# Spring2020V1_2.net
KiCad netlist of a schematic drawn in EAGLE
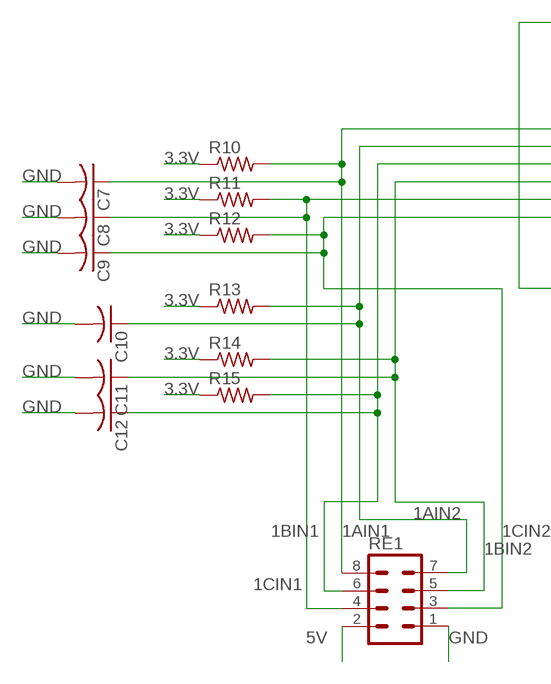
[diagram p0: schematic, sheet 1, part 1 of 2]
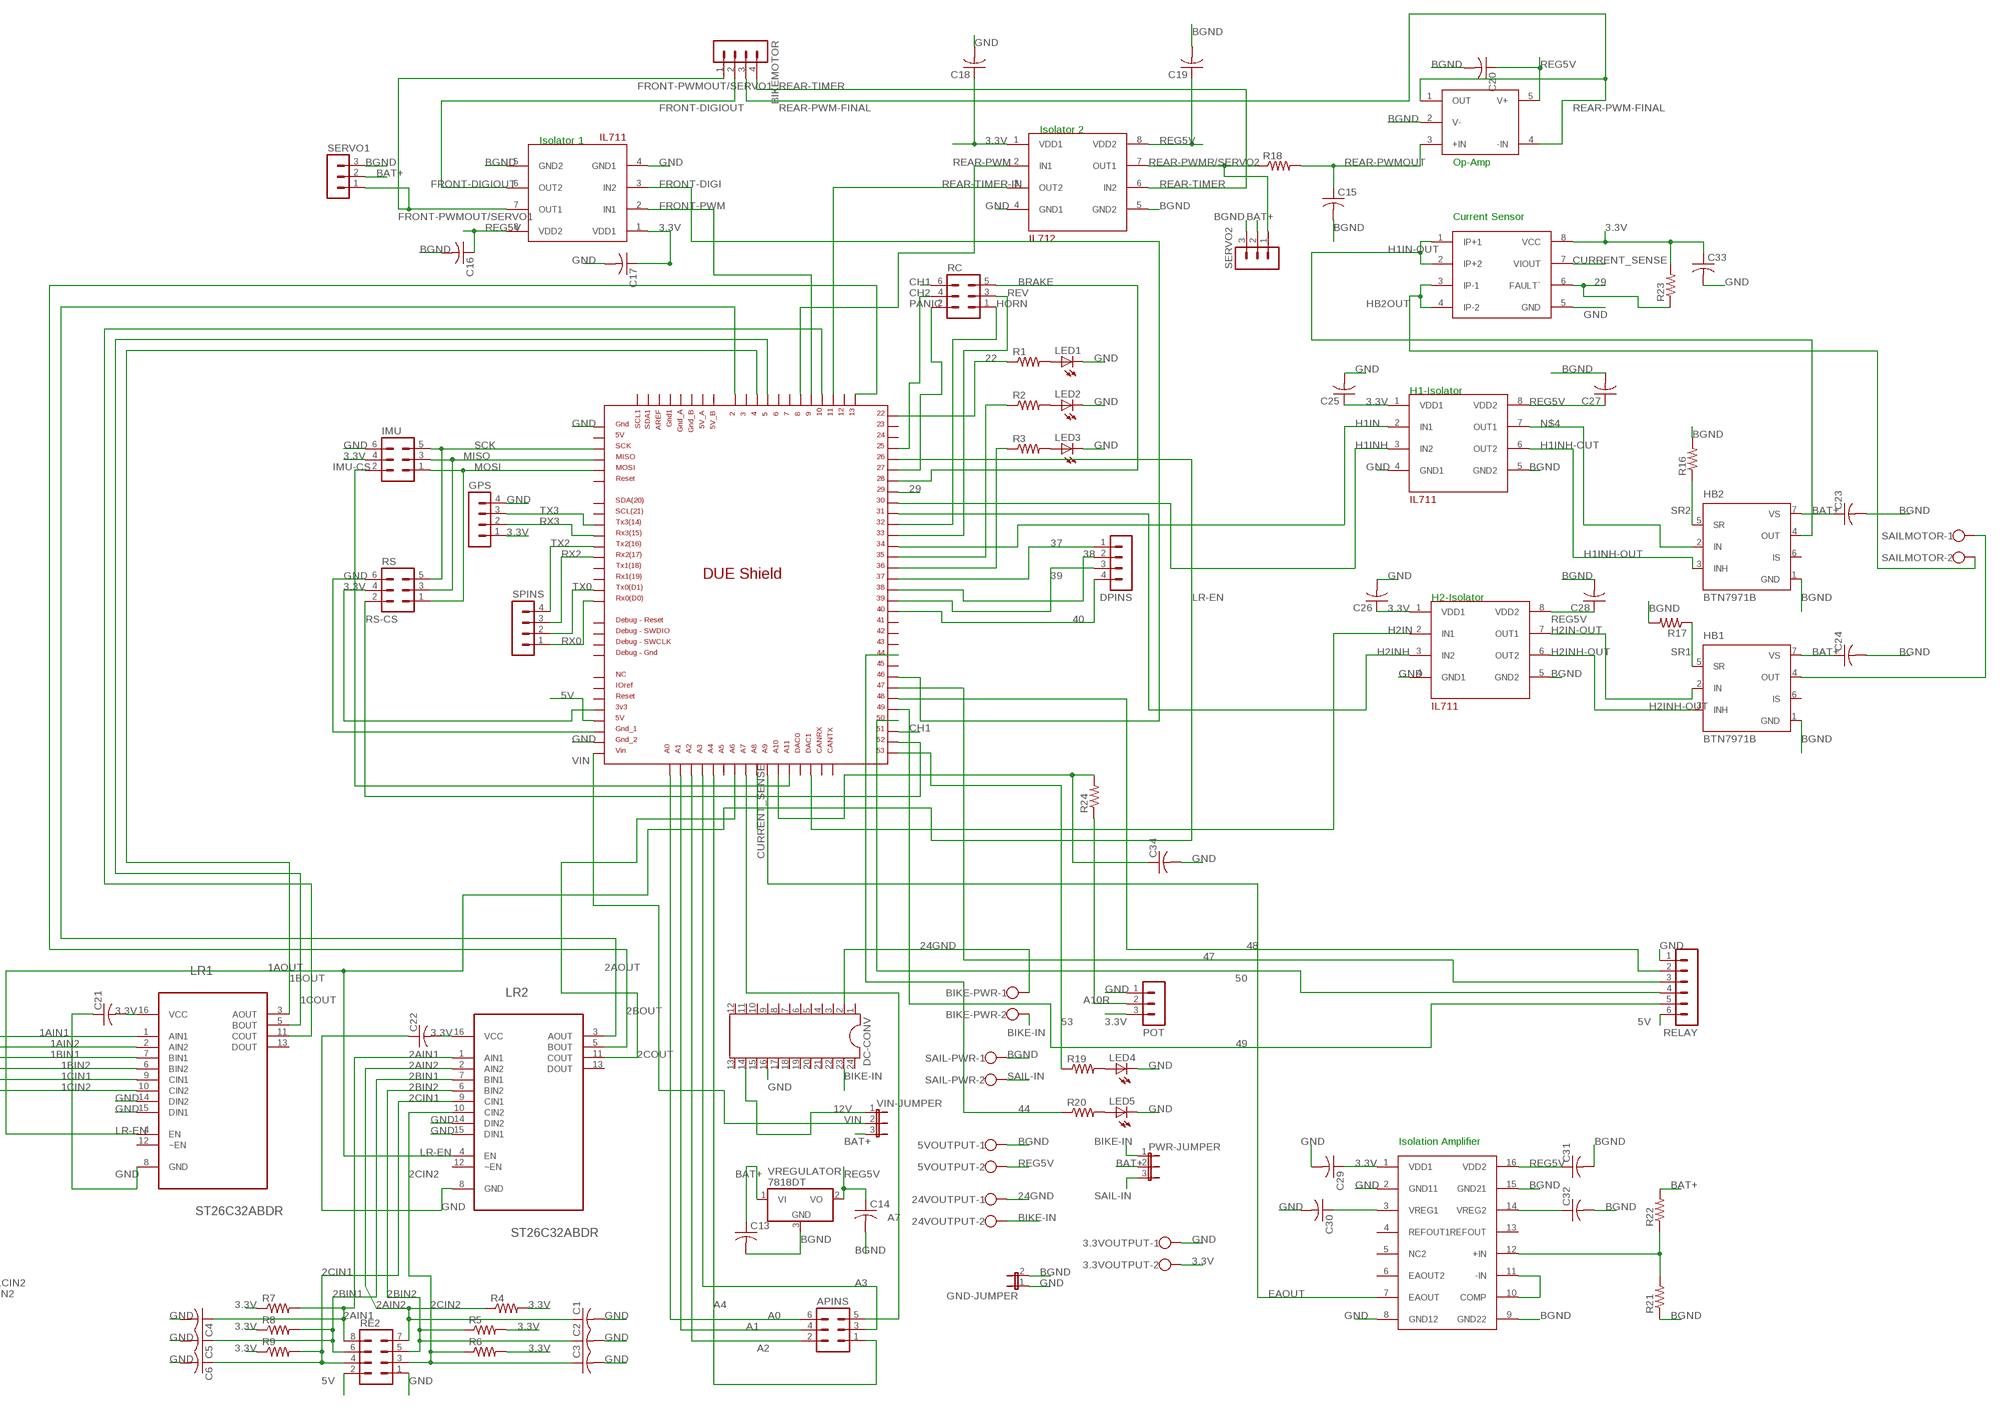
[diagram p1: schematic, sheet 1, part 2 of 2]

(export (version "E")
  (design (tool "Eeschema 10.0.6"))
  (components
    (comp (ref "3.3VOUTPUT")
      (value "W237-102")
      (footprint "eagle-import:W237-102")
      (fields (field (name "MPN") "237-102"))
      (libsource (lib "eagle-import") (part "W237-102"))
    )
    (comp (ref "5VOUTPUT")
      (value "W237-102")
      (footprint "eagle-import:W237-102")
      (fields (field (name "MPN") "237-102"))
      (libsource (lib "eagle-import") (part "W237-102"))
    )
    (comp (ref "24VOUTPUT")
      (value "W237-102")
      (footprint "eagle-import:W237-102")
      (fields (field (name "MPN") "237-102"))
      (libsource (lib "eagle-import") (part "W237-102"))
    )
    (comp (ref "APINS")
      (value "MA03-2")
      (footprint "eagle-import:MA03-2")
      (libsource (lib "eagle-import") (part "MA03-2"))
    )
    (comp (ref "BIKE-PWR")
      (value "W237-102")
      (footprint "eagle-import:W237-102")
      (fields (field (name "MPN") "237-102"))
      (libsource (lib "eagle-import") (part "W237-102"))
    )
    (comp (ref "BIKEMOTOR")
      (value "MA04-1")
      (footprint "eagle-import:MA04-1")
      (libsource (lib "eagle-import") (part "MA04-1"))
    )
    (comp (ref "C1")
      (value "C-US025-025X050")
      (footprint "eagle-import:C025-025X050")
      (libsource (lib "eagle-import") (part "C-US025-025X050"))
    )
    (comp (ref "C2")
      (value "C-US025-025X050")
      (footprint "eagle-import:C025-025X050")
      (libsource (lib "eagle-import") (part "C-US025-025X050"))
    )
    (comp (ref "C3")
      (value "C-US025-025X050")
      (footprint "eagle-import:C025-025X050")
      (libsource (lib "eagle-import") (part "C-US025-025X050"))
    )
    (comp (ref "C4")
      (value "C-US025-025X050")
      (footprint "eagle-import:C025-025X050")
      (libsource (lib "eagle-import") (part "C-US025-025X050"))
    )
    (comp (ref "C5")
      (value "C-US025-025X050")
      (footprint "eagle-import:C025-025X050")
      (libsource (lib "eagle-import") (part "C-US025-025X050"))
    )
    (comp (ref "C6")
      (value "C-US025-025X050")
      (footprint "eagle-import:C025-025X050")
      (libsource (lib "eagle-import") (part "C-US025-025X050"))
    )
    (comp (ref "C7")
      (value "C-US025-025X050")
      (footprint "eagle-import:C025-025X050")
      (libsource (lib "eagle-import") (part "C-US025-025X050"))
    )
    (comp (ref "C8")
      (value "C-US025-025X050")
      (footprint "eagle-import:C025-025X050")
      (libsource (lib "eagle-import") (part "C-US025-025X050"))
    )
    (comp (ref "C9")
      (value "C-US025-025X050")
      (footprint "eagle-import:C025-025X050")
      (libsource (lib "eagle-import") (part "C-US025-025X050"))
    )
    (comp (ref "C10")
      (value "C-US025-025X050")
      (footprint "eagle-import:C025-025X050")
      (libsource (lib "eagle-import") (part "C-US025-025X050"))
    )
    (comp (ref "C11")
      (value "C-US025-025X050")
      (footprint "eagle-import:C025-025X050")
      (libsource (lib "eagle-import") (part "C-US025-025X050"))
    )
    (comp (ref "C12")
      (value "C-US025-025X050")
      (footprint "eagle-import:C025-025X050")
      (libsource (lib "eagle-import") (part "C-US025-025X050"))
    )
    (comp (ref "C13")
      (value "C-US025-050X050")
      (footprint "eagle-import:C025-050X050")
      (libsource (lib "eagle-import") (part "C-US025-050X050"))
    )
    (comp (ref "C14")
      (value "C-US025-050X050")
      (footprint "eagle-import:C025-050X050")
      (libsource (lib "eagle-import") (part "C-US025-050X050"))
    )
    (comp (ref "C15")
      (value "C-US025-050X050")
      (footprint "eagle-import:C025-050X050")
      (libsource (lib "eagle-import") (part "C-US025-050X050"))
    )
    (comp (ref "C16")
      (value "C-US025-050X050")
      (footprint "eagle-import:C025-050X050")
      (libsource (lib "eagle-import") (part "C-US025-050X050"))
    )
    (comp (ref "C17")
      (value "C-US025-050X050")
      (footprint "eagle-import:C025-050X050")
      (libsource (lib "eagle-import") (part "C-US025-050X050"))
    )
    (comp (ref "C18")
      (value "C-US025-050X050")
      (footprint "eagle-import:C025-050X050")
      (libsource (lib "eagle-import") (part "C-US025-050X050"))
    )
    (comp (ref "C19")
      (value "C-US025-050X050")
      (footprint "eagle-import:C025-050X050")
      (libsource (lib "eagle-import") (part "C-US025-050X050"))
    )
    (comp (ref "C20")
      (value "C-US025-050X050")
      (footprint "eagle-import:C025-050X050")
      (libsource (lib "eagle-import") (part "C-US025-050X050"))
    )
    (comp (ref "C21")
      (value "C-US025-050X050")
      (footprint "eagle-import:C025-050X050")
      (libsource (lib "eagle-import") (part "C-US025-050X050"))
    )
    (comp (ref "C22")
      (value "C-US025-050X050")
      (footprint "eagle-import:C025-050X050")
      (libsource (lib "eagle-import") (part "C-US025-050X050"))
    )
    (comp (ref "C23")
      (value "C-US150-091X182")
      (footprint "eagle-import:C150-091X182")
      (libsource (lib "eagle-import") (part "C-US150-091X182"))
    )
    (comp (ref "C24")
      (value "C-US150-091X182")
      (footprint "eagle-import:C150-091X182")
      (libsource (lib "eagle-import") (part "C-US150-091X182"))
    )
    (comp (ref "C25")
      (value "C-US025-050X050")
      (footprint "eagle-import:C025-050X050")
      (libsource (lib "eagle-import") (part "C-US025-050X050"))
    )
    (comp (ref "C26")
      (value "C-US025-050X050")
      (footprint "eagle-import:C025-050X050")
      (libsource (lib "eagle-import") (part "C-US025-050X050"))
    )
    (comp (ref "C27")
      (value "C-US025-050X050")
      (footprint "eagle-import:C025-050X050")
      (libsource (lib "eagle-import") (part "C-US025-050X050"))
    )
    (comp (ref "C28")
      (value "C-US025-050X050")
      (footprint "eagle-import:C025-050X050")
      (libsource (lib "eagle-import") (part "C-US025-050X050"))
    )
    (comp (ref "C29")
      (value "C-US025-050X050")
      (footprint "eagle-import:C025-050X050")
      (libsource (lib "eagle-import") (part "C-US025-050X050"))
    )
    (comp (ref "C30")
      (value "C-US025-050X050")
      (footprint "eagle-import:C025-050X050")
      (libsource (lib "eagle-import") (part "C-US025-050X050"))
    )
    (comp (ref "C31")
      (value "C-US025-050X050")
      (footprint "eagle-import:C025-050X050")
      (libsource (lib "eagle-import") (part "C-US025-050X050"))
    )
    (comp (ref "C32")
      (value "C-US025-050X050")
      (footprint "eagle-import:C025-050X050")
      (libsource (lib "eagle-import") (part "C-US025-050X050"))
    )
    (comp (ref "C33")
      (value "C-US025-050X050")
      (footprint "eagle-import:C025-050X050")
      (libsource (lib "eagle-import") (part "C-US025-050X050"))
    )
    (comp (ref "C34")
      (value "C-US025-050X050")
      (footprint "eagle-import:C025-050X050")
      (libsource (lib "eagle-import") (part "C-US025-050X050"))
    )
    (comp (ref "DC-CONV")
      (value "CU.INC---VAWQ6-Q48-S12H-6")
      (footprint "eagle-import:DIL24-6")
      (libsource (lib "eagle-import") (part "CU.INC---VAWQ6-Q48-S12H-6"))
    )
    (comp (ref "DPINS")
      (value "MA04-1")
      (footprint "eagle-import:MA04-1")
      (libsource (lib "eagle-import") (part "MA04-1"))
    )
    (comp (ref "GND-JUMPER")
      (value "JP1E")
      (footprint "eagle-import:JP1")
      (libsource (lib "eagle-import") (part "JP1E"))
    )
    (comp (ref "GPS")
      (value "MA04-1")
      (footprint "eagle-import:MA04-1")
      (libsource (lib "eagle-import") (part "MA04-1"))
    )
    (comp (ref "HB1")
      (value "BTN7971B")
      (footprint "eagle-import:P-TO263-7-1")
      (libsource (lib "eagle-import") (part "BTN7971B"))
    )
    (comp (ref "HB2")
      (value "BTN7971B")
      (footprint "eagle-import:P-TO263-7-1")
      (libsource (lib "eagle-import") (part "BTN7971B"))
    )
    (comp (ref "IMU")
      (value "MA03-2")
      (footprint "eagle-import:MA03-2")
      (libsource (lib "eagle-import") (part "MA03-2"))
    )
    (comp (ref "LED1")
      (value "LED5MM")
      (footprint "eagle-import:LED5MM")
      (libsource (lib "eagle-import") (part "LED5MM"))
    )
    (comp (ref "LED2")
      (value "LED5MM")
      (footprint "eagle-import:LED5MM")
      (libsource (lib "eagle-import") (part "LED5MM"))
    )
    (comp (ref "LED3")
      (value "LED5MM")
      (footprint "eagle-import:LED5MM")
      (libsource (lib "eagle-import") (part "LED5MM"))
    )
    (comp (ref "LED4")
      (value "LED5MM")
      (footprint "eagle-import:LED5MM")
      (libsource (lib "eagle-import") (part "LED5MM"))
    )
    (comp (ref "LED5")
      (value "LED5MM")
      (footprint "eagle-import:LED5MM")
      (libsource (lib "eagle-import") (part "LED5MM"))
    )
    (comp (ref "LR1")
      (value "ST26C32ABDR")
      (footprint "eagle-import:SOIC127P600X175-16N")
      (libsource (lib "eagle-import") (part "ST26C32ABDR"))
    )
    (comp (ref "LR2")
      (value "ST26C32ABDR")
      (footprint "eagle-import:SOIC127P600X175-16N")
      (libsource (lib "eagle-import") (part "ST26C32ABDR"))
    )
    (comp (ref "OP-AMP")
      (value "OPAMP")
      (footprint "eagle-import:SOT95P280X145-5N")
      (libsource (lib "eagle-import") (part "OPAMP"))
    )
    (comp (ref "POT")
      (value "MA03-1")
      (footprint "eagle-import:MA03-1")
      (libsource (lib "eagle-import") (part "MA03-1"))
    )
    (comp (ref "PWR-JUMPER")
      (value "JP2E")
      (footprint "eagle-import:JP2")
      (libsource (lib "eagle-import") (part "JP2E"))
    )
    (comp (ref "R1")
      (value "R-US_0309/10")
      (footprint "eagle-import:0309_10")
      (libsource (lib "eagle-import") (part "R-US_0309/10"))
    )
    (comp (ref "R2")
      (value "R-US_0309/10")
      (footprint "eagle-import:0309_10")
      (libsource (lib "eagle-import") (part "R-US_0309/10"))
    )
    (comp (ref "R3")
      (value "R-US_0309/10")
      (footprint "eagle-import:0309_10")
      (libsource (lib "eagle-import") (part "R-US_0309/10"))
    )
    (comp (ref "R4")
      (value "R-US_0613/15")
      (footprint "eagle-import:P0613_15")
      (libsource (lib "eagle-import") (part "resistor_R-US_0613/15"))
    )
    (comp (ref "R5")
      (value "R-US_0613/15")
      (footprint "eagle-import:P0613_15")
      (libsource (lib "eagle-import") (part "resistor_R-US_0613/15"))
    )
    (comp (ref "R6")
      (value "R-US_0613/15")
      (footprint "eagle-import:P0613_15")
      (libsource (lib "eagle-import") (part "resistor_R-US_0613/15"))
    )
    (comp (ref "R7")
      (value "R-US_0613/15")
      (footprint "eagle-import:P0613_15")
      (libsource (lib "eagle-import") (part "resistor_R-US_0613/15"))
    )
    (comp (ref "R8")
      (value "R-US_0613/15")
      (footprint "eagle-import:P0613_15")
      (libsource (lib "eagle-import") (part "resistor_R-US_0613/15"))
    )
    (comp (ref "R9")
      (value "R-US_0613/15")
      (footprint "eagle-import:P0613_15")
      (libsource (lib "eagle-import") (part "resistor_R-US_0613/15"))
    )
    (comp (ref "R10")
      (value "R-US_0613/15")
      (footprint "eagle-import:P0613_15")
      (libsource (lib "eagle-import") (part "resistor_R-US_0613/15"))
    )
    (comp (ref "R11")
      (value "R-US_0613/15")
      (footprint "eagle-import:P0613_15")
      (libsource (lib "eagle-import") (part "resistor_R-US_0613/15"))
    )
    (comp (ref "R12")
      (value "R-US_0613/15")
      (footprint "eagle-import:P0613_15")
      (libsource (lib "eagle-import") (part "resistor_R-US_0613/15"))
    )
    (comp (ref "R13")
      (value "R-US_0613/15")
      (footprint "eagle-import:P0613_15")
      (libsource (lib "eagle-import") (part "resistor_R-US_0613/15"))
    )
    (comp (ref "R14")
      (value "R-US_0613/15")
      (footprint "eagle-import:P0613_15")
      (libsource (lib "eagle-import") (part "resistor_R-US_0613/15"))
    )
    (comp (ref "R15")
      (value "R-US_0613/15")
      (footprint "eagle-import:P0613_15")
      (libsource (lib "eagle-import") (part "resistor_R-US_0613/15"))
    )
    (comp (ref "R16")
      (value "R-US_0613/15")
      (footprint "eagle-import:P0613_15")
      (libsource (lib "eagle-import") (part "resistor_R-US_0613/15"))
    )
    (comp (ref "R17")
      (value "R-US_0613/15")
      (footprint "eagle-import:P0613_15")
      (libsource (lib "eagle-import") (part "resistor_R-US_0613/15"))
    )
    (comp (ref "R18")
      (value "R-US_0414/15")
      (footprint "eagle-import:0414_15")
      (libsource (lib "eagle-import") (part "resistor_R-US_0414/15"))
    )
    (comp (ref "R19")
      (value "R-US_0309/10")
      (footprint "eagle-import:0309_10")
      (libsource (lib "eagle-import") (part "R-US_0309/10"))
    )
    (comp (ref "R20")
      (value "R-US_0309/10")
      (footprint "eagle-import:0309_10")
      (libsource (lib "eagle-import") (part "R-US_0309/10"))
    )
    (comp (ref "R21")
      (value "R-US_0414/15")
      (footprint "eagle-import:0414_15")
      (libsource (lib "eagle-import") (part "resistor_R-US_0414/15"))
    )
    (comp (ref "R22")
      (value "R-US_0414/15")
      (footprint "eagle-import:0414_15")
      (libsource (lib "eagle-import") (part "resistor_R-US_0414/15"))
    )
    (comp (ref "R23")
      (value "R-US_0414/15")
      (footprint "eagle-import:0414_15")
      (libsource (lib "eagle-import") (part "resistor_R-US_0414/15"))
    )
    (comp (ref "R24")
      (value "R-US_0414/15")
      (footprint "eagle-import:0414_15")
      (libsource (lib "eagle-import") (part "resistor_R-US_0414/15"))
    )
    (comp (ref "RC")
      (value "MA03-2")
      (footprint "eagle-import:MA03-2")
      (libsource (lib "eagle-import") (part "MA03-2"))
    )
    (comp (ref "RE1")
      (value "MA04-2")
      (footprint "eagle-import:MA04-2")
      (libsource (lib "eagle-import") (part "MA04-2"))
    )
    (comp (ref "RE2")
      (value "MA04-2")
      (footprint "eagle-import:MA04-2")
      (libsource (lib "eagle-import") (part "MA04-2"))
    )
    (comp (ref "RELAY")
      (value "MA06-1")
      (footprint "eagle-import:MA06-1")
      (libsource (lib "eagle-import") (part "MA06-1"))
    )
    (comp (ref "RS")
      (value "MA03-2")
      (footprint "eagle-import:MA03-2")
      (libsource (lib "eagle-import") (part "MA03-2"))
    )
    (comp (ref "SAIL-PWR")
      (value "W237-102")
      (footprint "eagle-import:W237-102")
      (fields (field (name "MPN") "237-102"))
      (libsource (lib "eagle-import") (part "W237-102"))
    )
    (comp (ref "SAILMOTOR")
      (value "W237-102")
      (footprint "eagle-import:W237-102")
      (fields (field (name "MPN") "237-102"))
      (libsource (lib "eagle-import") (part "W237-102"))
    )
    (comp (ref "SERVO1")
      (value "MA03-1")
      (footprint "eagle-import:MA03-1")
      (libsource (lib "eagle-import") (part "MA03-1"))
    )
    (comp (ref "SERVO2")
      (value "MA03-1")
      (footprint "eagle-import:MA03-1")
      (libsource (lib "eagle-import") (part "MA03-1"))
    )
    (comp (ref "SPINS")
      (value "MA04-1")
      (footprint "eagle-import:MA04-1")
      (libsource (lib "eagle-import") (part "MA04-1"))
    )
    (comp (ref "U$1")
      (value "DUE(NORMAL)")
      (footprint "eagle-import:DUE(NORMAL)")
      (libsource (lib "eagle-import") (part "DUE(NORMAL)"))
    )
    (comp (ref "U$2")
      (value "IL-711")
      (footprint "eagle-import:8PINSOIC")
      (libsource (lib "eagle-import") (part "IL-711"))
    )
    (comp (ref "U$3")
      (value "IL-711")
      (footprint "eagle-import:8PINSOIC")
      (libsource (lib "eagle-import") (part "IL-711"))
    )
    (comp (ref "U$5")
      (value "ISOLATED_ERROR_AMP_ADUM3190")
      (footprint "eagle-import:QSOP16")
      (libsource (lib "eagle-import") (part "ISOLATED_ERROR_AMP_ADUM3190"))
    )
    (comp (ref "U$6")
      (value "IL-711")
      (footprint "eagle-import:8PINSOIC")
      (libsource (lib "eagle-import") (part "IL-711"))
    )
    (comp (ref "U$7")
      (value "IL-712")
      (footprint "eagle-import:8PINSOIC")
      (libsource (lib "eagle-import") (part "IL-712"))
    )
    (comp (ref "U$8")
      (value "LINEAR_CURRENT_SENSOR_ACS711")
      (footprint "eagle-import:SO8")
      (libsource (lib "eagle-import") (part "LINEAR_CURRENT_SENSOR_ACS711"))
    )
    (comp (ref "VIN-JUMPER")
      (value "JP2E")
      (footprint "eagle-import:JP2")
      (libsource (lib "eagle-import") (part "JP2E"))
    )
    (comp (ref "VREGULATOR")
      (value "7818DT")
      (footprint "eagle-import:TO252")
      (libsource (lib "eagle-import") (part "78DT18"))
    )
  )
  (nets
    (net (code "1") (name "/1AIN1") (class "Default")
      (node (ref "C7") (pin "1") (pinfunction "1_1") (pintype "passive"))
      (node (ref "LR1") (pin "1") (pinfunction "AIN1_1") (pintype "input"))
      (node (ref "R10") (pin "2") (pinfunction "2_2") (pintype "passive"))
      (node (ref "RE1") (pin "8") (pinfunction "8_8") (pintype "passive"))
    )
    (net (code "2") (name "/1AIN2") (class "Default")
      (node (ref "C10") (pin "1") (pinfunction "1_1") (pintype "passive"))
      (node (ref "LR1") (pin "2") (pinfunction "AIN2_2") (pintype "input"))
      (node (ref "R13") (pin "2") (pinfunction "2_2") (pintype "passive"))
      (node (ref "RE1") (pin "7") (pinfunction "7_7") (pintype "passive"))
    )
    (net (code "3") (name "/1AOUT") (class "Default")
      (node (ref "LR1") (pin "3") (pinfunction "AOUT_3") (pintype "output"))
      (node (ref "U$1") (pin "4") (pinfunction "4_4") (pintype "bidirectional"))
    )
    (net (code "4") (name "/1BIN1") (class "Default")
      (node (ref "C12") (pin "1") (pinfunction "1_1") (pintype "passive"))
      (node (ref "LR1") (pin "7") (pinfunction "BIN1_7") (pintype "input"))
      (node (ref "R15") (pin "2") (pinfunction "2_2") (pintype "passive"))
      (node (ref "RE1") (pin "6") (pinfunction "6_6") (pintype "passive"))
    )
    (net (code "5") (name "/1BIN2") (class "Default")
      (node (ref "C11") (pin "1") (pinfunction "1_1") (pintype "passive"))
      (node (ref "LR1") (pin "6") (pinfunction "BIN2_6") (pintype "input"))
      (node (ref "R14") (pin "2") (pinfunction "2_2") (pintype "passive"))
      (node (ref "RE1") (pin "5") (pinfunction "5_5") (pintype "passive"))
    )
    (net (code "6") (name "/1BOUT") (class "Default")
      (node (ref "LR1") (pin "5") (pinfunction "BOUT_5") (pintype "output"))
      (node (ref "U$1") (pin "5") (pinfunction "5_5") (pintype "bidirectional"))
    )
    (net (code "7") (name "/1CIN1") (class "Default")
      (node (ref "C8") (pin "1") (pinfunction "1_1") (pintype "passive"))
      (node (ref "LR1") (pin "9") (pinfunction "CIN1_9") (pintype "input"))
      (node (ref "R11") (pin "2") (pinfunction "2_2") (pintype "passive"))
      (node (ref "RE1") (pin "4") (pinfunction "4_4") (pintype "passive"))
    )
    (net (code "8") (name "/1CIN2") (class "Default")
      (node (ref "C9") (pin "1") (pinfunction "1_1") (pintype "passive"))
      (node (ref "LR1") (pin "10") (pinfunction "CIN2_10") (pintype "input"))
      (node (ref "R12") (pin "2") (pinfunction "2_2") (pintype "passive"))
      (node (ref "RE1") (pin "3") (pinfunction "3_3") (pintype "passive"))
    )
    (net (code "9") (name "/1COUT") (class "Default")
      (node (ref "LR1") (pin "11") (pinfunction "COUT_11") (pintype "output"))
      (node (ref "U$1") (pin "10") (pinfunction "10_10") (pintype "bidirectional"))
    )
    (net (code "10") (name "/2AIN1") (class "Default")
      (node (ref "C4") (pin "1") (pinfunction "1_1") (pintype "passive"))
      (node (ref "LR2") (pin "1") (pinfunction "AIN1_1") (pintype "input"))
      (node (ref "R7") (pin "2") (pinfunction "2_2") (pintype "passive"))
      (node (ref "RE2") (pin "8") (pinfunction "8_8") (pintype "passive"))
    )
    (net (code "11") (name "/2AIN2") (class "Default")
      (node (ref "C1") (pin "1") (pinfunction "1_1") (pintype "passive"))
      (node (ref "LR2") (pin "2") (pinfunction "AIN2_2") (pintype "input"))
      (node (ref "R4") (pin "1") (pinfunction "1_1") (pintype "passive"))
      (node (ref "RE2") (pin "7") (pinfunction "7_7") (pintype "passive"))
    )
    (net (code "12") (name "/2AOUT") (class "Default")
      (node (ref "LR2") (pin "3") (pinfunction "AOUT_3") (pintype "output"))
      (node (ref "U$1") (pin "2") (pinfunction "2_2") (pintype "bidirectional"))
    )
    (net (code "13") (name "/2BIN1") (class "Default")
      (node (ref "C5") (pin "1") (pinfunction "1_1") (pintype "passive"))
      (node (ref "LR2") (pin "7") (pinfunction "BIN1_7") (pintype "input"))
      (node (ref "R8") (pin "2") (pinfunction "2_2") (pintype "passive"))
      (node (ref "RE2") (pin "6") (pinfunction "6_6") (pintype "passive"))
    )
    (net (code "14") (name "/2BIN2") (class "Default")
      (node (ref "C2") (pin "1") (pinfunction "1_1") (pintype "passive"))
      (node (ref "LR2") (pin "6") (pinfunction "BIN2_6") (pintype "input"))
      (node (ref "R5") (pin "1") (pinfunction "1_1") (pintype "passive"))
      (node (ref "RE2") (pin "5") (pinfunction "5_5") (pintype "passive"))
    )
    (net (code "15") (name "/2BOUT") (class "Default")
      (node (ref "LR2") (pin "5") (pinfunction "BOUT_5") (pintype "output"))
      (node (ref "U$1") (pin "13") (pinfunction "13_13") (pintype "bidirectional"))
    )
    (net (code "16") (name "/2CIN1") (class "Default")
      (node (ref "C6") (pin "1") (pinfunction "1_1") (pintype "passive"))
      (node (ref "LR2") (pin "9") (pinfunction "CIN1_9") (pintype "input"))
      (node (ref "R9") (pin "2") (pinfunction "2_2") (pintype "passive"))
      (node (ref "RE2") (pin "4") (pinfunction "4_4") (pintype "passive"))
    )
    (net (code "17") (name "/2CIN2") (class "Default")
      (node (ref "C3") (pin "1") (pinfunction "1_1") (pintype "passive"))
      (node (ref "LR2") (pin "10") (pinfunction "CIN2_10") (pintype "input"))
      (node (ref "R6") (pin "1") (pinfunction "1_1") (pintype "passive"))
      (node (ref "RE2") (pin "3") (pinfunction "3_3") (pintype "passive"))
    )
    (net (code "18") (name "/2COUT") (class "Default")
      (node (ref "LR2") (pin "11") (pinfunction "COUT_11") (pintype "output"))
      (node (ref "U$1") (pin "A6") (pinfunction "A6_A6") (pintype "bidirectional"))
    )
    (net (code "19") (name "/3.3V") (class "Default")
      (node (ref "3.3VOUTPUT") (pin "2") (pinfunction "KL_2") (pintype "passive"))
      (node (ref "C17") (pin "1") (pinfunction "1_1") (pintype "passive"))
      (node (ref "C18") (pin "1") (pinfunction "1_1") (pintype "passive"))
      (node (ref "C21") (pin "2") (pinfunction "2_2") (pintype "passive"))
      (node (ref "C22") (pin "2") (pinfunction "2_2") (pintype "passive"))
      (node (ref "C25") (pin "1") (pinfunction "1_1") (pintype "passive"))
      (node (ref "C26") (pin "1") (pinfunction "1_1") (pintype "passive"))
      (node (ref "C29") (pin "1") (pinfunction "1_1") (pintype "passive"))
      (node (ref "C33") (pin "1") (pinfunction "1_1") (pintype "passive"))
      (node (ref "GPS") (pin "1") (pinfunction "1_1") (pintype "passive"))
      (node (ref "IMU") (pin "4") (pinfunction "4_4") (pintype "passive"))
      (node (ref "LR1") (pin "16") (pinfunction "VCC_16") (pintype "power_in"))
      (node (ref "LR2") (pin "16") (pinfunction "VCC_16") (pintype "power_in"))
      (node (ref "POT") (pin "3") (pinfunction "3_3") (pintype "passive"))
      (node (ref "R10") (pin "1") (pinfunction "1_1") (pintype "passive"))
      (node (ref "R11") (pin "1") (pinfunction "1_1") (pintype "passive"))
      (node (ref "R12") (pin "1") (pinfunction "1_1") (pintype "passive"))
      (node (ref "R13") (pin "1") (pinfunction "1_1") (pintype "passive"))
      (node (ref "R14") (pin "1") (pinfunction "1_1") (pintype "passive"))
      (node (ref "R15") (pin "1") (pinfunction "1_1") (pintype "passive"))
      (node (ref "R23") (pin "2") (pinfunction "2_2") (pintype "passive"))
      (node (ref "R4") (pin "2") (pinfunction "2_2") (pintype "passive"))
      (node (ref "R5") (pin "2") (pinfunction "2_2") (pintype "passive"))
      (node (ref "R6") (pin "2") (pinfunction "2_2") (pintype "passive"))
      (node (ref "R7") (pin "1") (pinfunction "1_1") (pintype "passive"))
      (node (ref "R8") (pin "1") (pinfunction "1_1") (pintype "passive"))
      (node (ref "R9") (pin "1") (pinfunction "1_1") (pintype "passive"))
      (node (ref "RS") (pin "4") (pinfunction "4_4") (pintype "passive"))
      (node (ref "U$1") (pin "3V3") (pinfunction "3V3_3V3") (pintype "bidirectional"))
      (node (ref "U$2") (pin "1") (pinfunction "VDD1_1") (pintype "power_in"))
      (node (ref "U$3") (pin "1") (pinfunction "VDD1_1") (pintype "power_in"))
      (node (ref "U$5") (pin "1") (pinfunction "VDD1_1") (pintype "bidirectional"))
      (node (ref "U$6") (pin "1") (pinfunction "VDD1_1") (pintype "power_in"))
      (node (ref "U$7") (pin "1") (pinfunction "VDD1_1") (pintype "power_in"))
      (node (ref "U$8") (pin "8") (pinfunction "VCC_8") (pintype "bidirectional"))
    )
    (net (code "20") (name "/5V") (class "Default")
      (node (ref "RE1") (pin "2") (pinfunction "2_2") (pintype "passive"))
      (node (ref "RE2") (pin "2") (pinfunction "2_2") (pintype "passive"))
      (node (ref "RELAY") (pin "6") (pinfunction "6_6") (pintype "passive"))
      (node (ref "U$1") (pin "5V") (pinfunction "5V_5V") (pintype "bidirectional"))
    )
    (net (code "21") (name "/12V") (class "Default")
      (node (ref "DC-CONV") (pin "14") (pinfunction "14_14") (pintype "passive"))
      (node (ref "VIN-JUMPER") (pin "1") (pinfunction "1_1") (pintype "passive"))
    )
    (net (code "22") (name "/22") (class "Default")
      (node (ref "R1") (pin "1") (pinfunction "1_1") (pintype "passive"))
      (node (ref "U$1") (pin "22") (pinfunction "22_22") (pintype "bidirectional"))
    )
    (net (code "23") (name "/24GND") (class "Default")
      (node (ref "24VOUTPUT") (pin "1") (pinfunction "KL_1") (pintype "passive"))
      (node (ref "BIKE-PWR") (pin "1") (pinfunction "KL_1") (pintype "passive"))
      (node (ref "DC-CONV") (pin "2") (pinfunction "2_2") (pintype "passive"))
    )
    (net (code "24") (name "/29") (class "Default")
      (node (ref "R23") (pin "1") (pinfunction "1_1") (pintype "passive"))
      (node (ref "U$1") (pin "29") (pinfunction "29_29") (pintype "bidirectional"))
      (node (ref "U$8") (pin "6") (pinfunction "FAULT`_6") (pintype "bidirectional"))
    )
    (net (code "25") (name "/37") (class "Default")
      (node (ref "DPINS") (pin "1") (pinfunction "1_1") (pintype "passive"))
      (node (ref "U$1") (pin "37") (pinfunction "37_37") (pintype "bidirectional"))
    )
    (net (code "26") (name "/38") (class "Default")
      (node (ref "DPINS") (pin "2") (pinfunction "2_2") (pintype "passive"))
      (node (ref "U$1") (pin "38") (pinfunction "38_38") (pintype "bidirectional"))
    )
    (net (code "27") (name "/39") (class "Default")
      (node (ref "DPINS") (pin "3") (pinfunction "3_3") (pintype "passive"))
      (node (ref "U$1") (pin "39") (pinfunction "39_39") (pintype "bidirectional"))
    )
    (net (code "28") (name "/40") (class "Default")
      (node (ref "DPINS") (pin "4") (pinfunction "4_4") (pintype "passive"))
      (node (ref "U$1") (pin "40") (pinfunction "40_40") (pintype "bidirectional"))
    )
    (net (code "29") (name "/44") (class "Default")
      (node (ref "R20") (pin "1") (pinfunction "1_1") (pintype "passive"))
      (node (ref "U$1") (pin "44") (pinfunction "44_44") (pintype "bidirectional"))
    )
    (net (code "30") (name "/47") (class "Default")
      (node (ref "RELAY") (pin "3") (pinfunction "3_3") (pintype "passive"))
      (node (ref "U$1") (pin "47") (pinfunction "47_47") (pintype "bidirectional"))
    )
    (net (code "31") (name "/48") (class "Default")
      (node (ref "RELAY") (pin "2") (pinfunction "2_2") (pintype "passive"))
      (node (ref "U$1") (pin "48") (pinfunction "48_48") (pintype "bidirectional"))
    )
    (net (code "32") (name "/49") (class "Default")
      (node (ref "RELAY") (pin "5") (pinfunction "5_5") (pintype "passive"))
      (node (ref "U$1") (pin "49") (pinfunction "49_49") (pintype "bidirectional"))
    )
    (net (code "33") (name "/50") (class "Default")
      (node (ref "RELAY") (pin "4") (pinfunction "4_4") (pintype "passive"))
      (node (ref "U$1") (pin "50") (pinfunction "50_50") (pintype "bidirectional"))
    )
    (net (code "34") (name "/53") (class "Default")
      (node (ref "R19") (pin "1") (pinfunction "1_1") (pintype "passive"))
      (node (ref "U$1") (pin "53") (pinfunction "53_53") (pintype "bidirectional"))
    )
    (net (code "35") (name "/A0") (class "Default")
      (node (ref "APINS") (pin "6") (pinfunction "6_6") (pintype "passive"))
      (node (ref "U$1") (pin "A0") (pinfunction "A0_A0") (pintype "bidirectional"))
    )
    (net (code "36") (name "/A1") (class "Default")
      (node (ref "APINS") (pin "4") (pinfunction "4_4") (pintype "passive"))
      (node (ref "U$1") (pin "A1") (pinfunction "A1_A1") (pintype "bidirectional"))
    )
    (net (code "37") (name "/A2") (class "Default")
      (node (ref "APINS") (pin "2") (pinfunction "2_2") (pintype "passive"))
      (node (ref "U$1") (pin "A2") (pinfunction "A2_A2") (pintype "bidirectional"))
    )
    (net (code "38") (name "/A3") (class "Default")
      (node (ref "APINS") (pin "3") (pinfunction "3_3") (pintype "passive"))
      (node (ref "U$1") (pin "A3") (pinfunction "A3_A3") (pintype "bidirectional"))
    )
    (net (code "39") (name "/A4") (class "Default")
      (node (ref "APINS") (pin "1") (pinfunction "1_1") (pintype "passive"))
      (node (ref "U$1") (pin "A4") (pinfunction "A4_A4") (pintype "bidirectional"))
    )
    (net (code "40") (name "/A7") (class "Default")
      (node (ref "APINS") (pin "5") (pinfunction "5_5") (pintype "passive"))
      (node (ref "U$1") (pin "A7") (pinfunction "A7_A7") (pintype "bidirectional"))
    )
    (net (code "41") (name "/A10R") (class "Default")
      (node (ref "POT") (pin "2") (pinfunction "2_2") (pintype "passive"))
      (node (ref "R24") (pin "1") (pinfunction "1_1") (pintype "passive"))
    )
    (net (code "42") (name "/BAT+") (class "Default")
      (node (ref "C13") (pin "1") (pinfunction "1_1") (pintype "passive"))
      (node (ref "C23") (pin "1") (pinfunction "1_1") (pintype "passive"))
      (node (ref "C24") (pin "1") (pinfunction "1_1") (pintype "passive"))
      (node (ref "HB1") (pin "7") (pinfunction "VS_7") (pintype "input"))
      (node (ref "HB2") (pin "7") (pinfunction "VS_7") (pintype "input"))
      (node (ref "PWR-JUMPER") (pin "2") (pinfunction "2_2") (pintype "passive"))
      (node (ref "R22") (pin "2") (pinfunction "2_2") (pintype "passive"))
      (node (ref "SERVO1") (pin "2") (pinfunction "2_2") (pintype "passive"))
      (node (ref "SERVO2") (pin "2") (pinfunction "2_2") (pintype "passive"))
      (node (ref "VIN-JUMPER") (pin "3") (pinfunction "3_3") (pintype "passive"))
      (node (ref "VREGULATOR") (pin "1") (pinfunction "VI_1") (pintype "input"))
    )
    (net (code "43") (name "/BGND") (class "Default")
      (node (ref "5VOUTPUT") (pin "1") (pinfunction "KL_1") (pintype "passive"))
      (node (ref "C13") (pin "2") (pinfunction "2_2") (pintype "passive"))
      (node (ref "C14") (pin "2") (pinfunction "2_2") (pintype "passive"))
      (node (ref "C15") (pin "2") (pinfunction "2_2") (pintype "passive"))
      (node (ref "C16") (pin "2") (pinfunction "2_2") (pintype "passive"))
      (node (ref "C19") (pin "2") (pinfunction "2_2") (pintype "passive"))
      (node (ref "C20") (pin "2") (pinfunction "2_2") (pintype "passive"))
      (node (ref "C23") (pin "2") (pinfunction "2_2") (pintype "passive"))
      (node (ref "C24") (pin "2") (pinfunction "2_2") (pintype "passive"))
      (node (ref "C27") (pin "2") (pinfunction "2_2") (pintype "passive"))
      (node (ref "C28") (pin "2") (pinfunction "2_2") (pintype "passive"))
      (node (ref "C31") (pin "2") (pinfunction "2_2") (pintype "passive"))
      (node (ref "C32") (pin "2") (pinfunction "2_2") (pintype "passive"))
      (node (ref "GND-JUMPER") (pin "2") (pinfunction "2_2") (pintype "passive"))
      (node (ref "HB1") (pin "1") (pinfunction "GND_1") (pintype "power_in"))
      (node (ref "HB2") (pin "1") (pinfunction "GND_1") (pintype "power_in"))
      (node (ref "OP-AMP") (pin "2") (pinfunction "V-_2") (pintype "output"))
      (node (ref "R16") (pin "2") (pinfunction "2_2") (pintype "passive"))
      (node (ref "R17") (pin "2") (pinfunction "2_2") (pintype "passive"))
      (node (ref "R21") (pin "1") (pinfunction "1_1") (pintype "passive"))
      (node (ref "SAIL-PWR") (pin "1") (pinfunction "KL_1") (pintype "passive"))
      (node (ref "SERVO1") (pin "3") (pinfunction "3_3") (pintype "passive"))
      (node (ref "SERVO2") (pin "3") (pinfunction "3_3") (pintype "passive"))
      (node (ref "U$2") (pin "5") (pinfunction "GND2_5") (pintype "power_in"))
      (node (ref "U$3") (pin "5") (pinfunction "GND2_5") (pintype "power_in"))
      (node (ref "U$5") (pin "15") (pinfunction "GND21_15") (pintype "bidirectional"))
      (node (ref "U$5") (pin "9") (pinfunction "GND22_9") (pintype "bidirectional"))
      (node (ref "U$6") (pin "5") (pinfunction "GND2_5") (pintype "power_in"))
      (node (ref "U$7") (pin "5") (pinfunction "GND2_5") (pintype "power_in"))
      (node (ref "VREGULATOR") (pin "3") (pinfunction "GND_3") (pintype "passive"))
    )
    (net (code "44") (name "/BIKE-IN") (class "Default")
      (node (ref "24VOUTPUT") (pin "2") (pinfunction "KL_2") (pintype "passive"))
      (node (ref "BIKE-PWR") (pin "2") (pinfunction "KL_2") (pintype "passive"))
      (node (ref "DC-CONV") (pin "23") (pinfunction "23_23") (pintype "passive"))
      (node (ref "PWR-JUMPER") (pin "1") (pinfunction "1_1") (pintype "passive"))
    )
    (net (code "45") (name "/BRAKE") (class "Default")
      (node (ref "RC") (pin "5") (pinfunction "5_5") (pintype "passive"))
      (node (ref "U$1") (pin "28") (pinfunction "28_28") (pintype "bidirectional"))
    )
    (net (code "46") (name "/CH1") (class "Default")
      (node (ref "RC") (pin "6") (pinfunction "6_6") (pintype "passive"))
      (node (ref "U$1") (pin "51") (pinfunction "51_51") (pintype "bidirectional"))
    )
    (net (code "47") (name "/CH2") (class "Default")
      (node (ref "RC") (pin "4") (pinfunction "4_4") (pintype "passive"))
      (node (ref "U$1") (pin "25") (pinfunction "25_25") (pintype "bidirectional"))
    )
    (net (code "48") (name "/CURRENT_SENSE") (class "Default")
      (node (ref "U$1") (pin "A8") (pinfunction "A8_A8") (pintype "bidirectional"))
      (node (ref "U$8") (pin "7") (pinfunction "VIOUT_7") (pintype "bidirectional"))
    )
    (net (code "49") (name "/EAOUT") (class "Default")
      (node (ref "U$1") (pin "A9") (pinfunction "A9_A9") (pintype "bidirectional"))
      (node (ref "U$5") (pin "7") (pinfunction "EAOUT_7") (pintype "bidirectional"))
    )
    (net (code "50") (name "/FRONT-DIGI") (class "Default")
      (node (ref "U$1") (pin "46") (pinfunction "46_46") (pintype "bidirectional"))
      (node (ref "U$2") (pin "3") (pinfunction "IN2_3") (pintype "input"))
    )
    (net (code "51") (name "/FRONT-DIGIOUT") (class "Default")
      (node (ref "BIKEMOTOR") (pin "2") (pinfunction "2_2") (pintype "passive"))
      (node (ref "U$2") (pin "6") (pinfunction "OUT2_6") (pintype "output"))
    )
    (net (code "52") (name "/FRONT-PWM") (class "Default")
      (node (ref "U$1") (pin "9") (pinfunction "9_9") (pintype "bidirectional"))
      (node (ref "U$2") (pin "2") (pinfunction "IN1_2") (pintype "input"))
    )
    (net (code "53") (name "/FRONT-PWMOUT{slash}SERVO1") (class "Default")
      (node (ref "BIKEMOTOR") (pin "1") (pinfunction "1_1") (pintype "passive"))
      (node (ref "SERVO1") (pin "1") (pinfunction "1_1") (pintype "passive"))
      (node (ref "U$2") (pin "7") (pinfunction "OUT1_7") (pintype "output"))
    )
    (net (code "54") (name "/GND") (class "Default")
      (node (ref "3.3VOUTPUT") (pin "1") (pinfunction "KL_1") (pintype "passive"))
      (node (ref "C1") (pin "2") (pinfunction "2_2") (pintype "passive"))
      (node (ref "C10") (pin "2") (pinfunction "2_2") (pintype "passive"))
      (node (ref "C11") (pin "2") (pinfunction "2_2") (pintype "passive"))
      (node (ref "C12") (pin "2") (pinfunction "2_2") (pintype "passive"))
      (node (ref "C17") (pin "2") (pinfunction "2_2") (pintype "passive"))
      (node (ref "C18") (pin "2") (pinfunction "2_2") (pintype "passive"))
      (node (ref "C2") (pin "2") (pinfunction "2_2") (pintype "passive"))
      (node (ref "C21") (pin "1") (pinfunction "1_1") (pintype "passive"))
      (node (ref "C22") (pin "1") (pinfunction "1_1") (pintype "passive"))
      (node (ref "C25") (pin "2") (pinfunction "2_2") (pintype "passive"))
      (node (ref "C26") (pin "2") (pinfunction "2_2") (pintype "passive"))
      (node (ref "C29") (pin "2") (pinfunction "2_2") (pintype "passive"))
      (node (ref "C3") (pin "2") (pinfunction "2_2") (pintype "passive"))
      (node (ref "C30") (pin "2") (pinfunction "2_2") (pintype "passive"))
      (node (ref "C33") (pin "2") (pinfunction "2_2") (pintype "passive"))
      (node (ref "C34") (pin "2") (pinfunction "2_2") (pintype "passive"))
      (node (ref "C4") (pin "2") (pinfunction "2_2") (pintype "passive"))
      (node (ref "C5") (pin "2") (pinfunction "2_2") (pintype "passive"))
      (node (ref "C6") (pin "2") (pinfunction "2_2") (pintype "passive"))
      (node (ref "C7") (pin "2") (pinfunction "2_2") (pintype "passive"))
      (node (ref "C8") (pin "2") (pinfunction "2_2") (pintype "passive"))
      (node (ref "C9") (pin "2") (pinfunction "2_2") (pintype "passive"))
      (node (ref "DC-CONV") (pin "16") (pinfunction "16_16") (pintype "passive"))
      (node (ref "GND-JUMPER") (pin "1") (pinfunction "1_1") (pintype "passive"))
      (node (ref "GPS") (pin "4") (pinfunction "4_4") (pintype "passive"))
      (node (ref "IMU") (pin "6") (pinfunction "6_6") (pintype "passive"))
      (node (ref "LED1") (pin "K") (pinfunction "C_K") (pintype "passive"))
      (node (ref "LED2") (pin "K") (pinfunction "C_K") (pintype "passive"))
      (node (ref "LED3") (pin "K") (pinfunction "C_K") (pintype "passive"))
      (node (ref "LED4") (pin "K") (pinfunction "C_K") (pintype "passive"))
      (node (ref "LED5") (pin "K") (pinfunction "C_K") (pintype "passive"))
      (node (ref "LR1") (pin "14") (pinfunction "DIN2_14") (pintype "input"))
      (node (ref "LR1") (pin "15") (pinfunction "DIN1_15") (pintype "input"))
      (node (ref "LR1") (pin "8") (pinfunction "GND_8") (pintype "passive"))
      (node (ref "LR2") (pin "14") (pinfunction "DIN2_14") (pintype "input"))
      (node (ref "LR2") (pin "15") (pinfunction "DIN1_15") (pintype "input"))
      (node (ref "LR2") (pin "8") (pinfunction "GND_8") (pintype "passive"))
      (node (ref "POT") (pin "1") (pinfunction "1_1") (pintype "passive"))
      (node (ref "RE1") (pin "1") (pinfunction "1_1") (pintype "passive"))
      (node (ref "RE2") (pin "1") (pinfunction "1_1") (pintype "passive"))
      (node (ref "RELAY") (pin "1") (pinfunction "1_1") (pintype "passive"))
      (node (ref "RS") (pin "6") (pinfunction "6_6") (pintype "passive"))
      (node (ref "U$1") (pin "5V_ICSP") (pinfunction "5V_ICSP_5V_ICSP") (pintype "bidirectional"))
      (node (ref "U$1") (pin "GND_1") (pinfunction "GND_1_GND_1") (pintype "bidirectional"))
      (node (ref "U$1") (pin "GND_2") (pinfunction "GND_2_GND_2") (pintype "bidirectional"))
      (node (ref "U$2") (pin "4") (pinfunction "GND1_4") (pintype "power_in"))
      (node (ref "U$3") (pin "4") (pinfunction "GND1_4") (pintype "power_in"))
      (node (ref "U$5") (pin "2") (pinfunction "GND11_2") (pintype "bidirectional"))
      (node (ref "U$5") (pin "8") (pinfunction "GND12_8") (pintype "bidirectional"))
      (node (ref "U$6") (pin "4") (pinfunction "GND1_4") (pintype "power_in"))
      (node (ref "U$7") (pin "4") (pinfunction "GND1_4") (pintype "power_in"))
      (node (ref "U$8") (pin "5") (pinfunction "GND_5") (pintype "bidirectional"))
    )
    (net (code "55") (name "/H1IN") (class "Default")
      (node (ref "U$1") (pin "34") (pinfunction "34_34") (pintype "bidirectional"))
      (node (ref "U$3") (pin "2") (pinfunction "IN1_2") (pintype "input"))
    )
    (net (code "56") (name "/H1IN-OUT") (class "Default")
      (node (ref "HB2") (pin "4") (pinfunction "OUT_4") (pintype "output"))
      (node (ref "U$8") (pin "1") (pinfunction "IP+1_1") (pintype "bidirectional"))
      (node (ref "U$8") (pin "2") (pinfunction "IP+2_2") (pintype "bidirectional"))
    )
    (net (code "57") (name "/H1INH") (class "Default")
      (node (ref "U$1") (pin "30") (pinfunction "30_30") (pintype "bidirectional"))
      (node (ref "U$3") (pin "3") (pinfunction "IN2_3") (pintype "input"))
    )
    (net (code "58") (name "/H1INH-OUT") (class "Default")
      (node (ref "HB2") (pin "3") (pinfunction "INH_3") (pintype "input"))
      (node (ref "U$3") (pin "6") (pinfunction "OUT2_6") (pintype "output"))
    )
    (net (code "59") (name "/H2IN") (class "Default")
      (node (ref "U$1") (pin "DAC1") (pinfunction "DAC1_DAC1") (pintype "bidirectional"))
      (node (ref "U$6") (pin "2") (pinfunction "IN1_2") (pintype "input"))
    )
    (net (code "60") (name "/H2IN-OUT") (class "Default")
      (node (ref "HB1") (pin "2") (pinfunction "IN_2") (pintype "input"))
      (node (ref "U$6") (pin "7") (pinfunction "OUT1_7") (pintype "output"))
    )
    (net (code "61") (name "/H2INH") (class "Default")
      (node (ref "U$1") (pin "31") (pinfunction "31_31") (pintype "bidirectional"))
      (node (ref "U$6") (pin "3") (pinfunction "IN2_3") (pintype "input"))
    )
    (net (code "62") (name "/H2INH-OUT") (class "Default")
      (node (ref "HB1") (pin "3") (pinfunction "INH_3") (pintype "input"))
      (node (ref "U$6") (pin "6") (pinfunction "OUT2_6") (pintype "output"))
    )
    (net (code "63") (name "/HB2OUT") (class "Default")
      (node (ref "SAILMOTOR") (pin "2") (pinfunction "KL_2") (pintype "passive"))
      (node (ref "U$8") (pin "3") (pinfunction "IP-1_3") (pintype "bidirectional"))
      (node (ref "U$8") (pin "4") (pinfunction "IP-2_4") (pintype "bidirectional"))
    )
    (net (code "64") (name "/HORN") (class "Default")
      (node (ref "RC") (pin "1") (pinfunction "1_1") (pintype "passive"))
      (node (ref "U$1") (pin "32") (pinfunction "32_32") (pintype "bidirectional"))
    )
    (net (code "65") (name "/IMU-CS") (class "Default")
      (node (ref "IMU") (pin "2") (pinfunction "2_2") (pintype "passive"))
      (node (ref "U$1") (pin "A11") (pinfunction "A11_A11") (pintype "bidirectional"))
    )
    (net (code "66") (name "/LR-EN") (class "Default")
      (node (ref "LR1") (pin "4") (pinfunction "EN_4") (pintype "input"))
      (node (ref "LR2") (pin "4") (pinfunction "EN_4") (pintype "input"))
      (node (ref "U$1") (pin "26") (pinfunction "26_26") (pintype "bidirectional"))
    )
    (net (code "67") (name "/MISO") (class "Default")
      (node (ref "IMU") (pin "3") (pinfunction "3_3") (pintype "passive"))
      (node (ref "RS") (pin "3") (pinfunction "3_3") (pintype "passive"))
      (node (ref "U$1") (pin "MISO_ICSP") (pinfunction "MISO_ICSP_MISO_ICSP") (pintype "bidirectional"))
    )
    (net (code "68") (name "/MOSI") (class "Default")
      (node (ref "IMU") (pin "1") (pinfunction "1_1") (pintype "passive"))
      (node (ref "RS") (pin "1") (pinfunction "1_1") (pintype "passive"))
      (node (ref "U$1") (pin "MOSI_ICSP") (pinfunction "MOSI_ICSP_MOSI_ICSP") (pintype "bidirectional"))
    )
    (net (code "69") (name "/N$4") (class "Default")
      (node (ref "HB2") (pin "2") (pinfunction "IN_2") (pintype "input"))
      (node (ref "U$3") (pin "7") (pinfunction "OUT1_7") (pintype "output"))
    )
    (net (code "70") (name "/PANIC") (class "Default")
      (node (ref "RC") (pin "2") (pinfunction "2_2") (pintype "passive"))
      (node (ref "U$1") (pin "27") (pinfunction "27_27") (pintype "bidirectional"))
    )
    (net (code "71") (name "/REAR-PWM") (class "Default")
      (node (ref "U$1") (pin "8") (pinfunction "8_8") (pintype "bidirectional"))
      (node (ref "U$7") (pin "2") (pinfunction "IN1_2") (pintype "input"))
    )
    (net (code "72") (name "/REAR-PWM-FINAL") (class "Default")
      (node (ref "BIKEMOTOR") (pin "3") (pinfunction "3_3") (pintype "passive"))
      (node (ref "OP-AMP") (pin "1") (pinfunction "OUT_1") (pintype "output"))
      (node (ref "OP-AMP") (pin "4") (pinfunction "-IN_4") (pintype "input"))
    )
    (net (code "73") (name "/REAR-PWMOUT") (class "Default")
      (node (ref "C15") (pin "1") (pinfunction "1_1") (pintype "passive"))
      (node (ref "OP-AMP") (pin "3") (pinfunction "+IN_3") (pintype "input"))
      (node (ref "R18") (pin "2") (pinfunction "2_2") (pintype "passive"))
    )
    (net (code "74") (name "/REAR-PWMR{slash}SERVO2") (class "Default")
      (node (ref "R18") (pin "1") (pinfunction "1_1") (pintype "passive"))
      (node (ref "SERVO2") (pin "1") (pinfunction "1_1") (pintype "passive"))
      (node (ref "U$7") (pin "7") (pinfunction "OUT1_7") (pintype "output"))
    )
    (net (code "75") (name "/REAR-TIMER") (class "Default")
      (node (ref "BIKEMOTOR") (pin "4") (pinfunction "4_4") (pintype "passive"))
      (node (ref "U$7") (pin "6") (pinfunction "IN2_6") (pintype "input"))
    )
    (net (code "76") (name "/REAR-TIMER-IN") (class "Default")
      (node (ref "U$1") (pin "11") (pinfunction "11_11") (pintype "bidirectional"))
      (node (ref "U$7") (pin "3") (pinfunction "OUT2_3") (pintype "output"))
    )
    (net (code "77") (name "/REG5V") (class "Default")
      (node (ref "5VOUTPUT") (pin "2") (pinfunction "KL_2") (pintype "passive"))
      (node (ref "C14") (pin "1") (pinfunction "1_1") (pintype "passive"))
      (node (ref "C16") (pin "1") (pinfunction "1_1") (pintype "passive"))
      (node (ref "C19") (pin "1") (pinfunction "1_1") (pintype "passive"))
      (node (ref "C20") (pin "1") (pinfunction "1_1") (pintype "passive"))
      (node (ref "C27") (pin "1") (pinfunction "1_1") (pintype "passive"))
      (node (ref "C28") (pin "1") (pinfunction "1_1") (pintype "passive"))
      (node (ref "C31") (pin "1") (pinfunction "1_1") (pintype "passive"))
      (node (ref "OP-AMP") (pin "5") (pinfunction "V+_5") (pintype "power_in"))
      (node (ref "U$2") (pin "8") (pinfunction "VDD2_8") (pintype "power_in"))
      (node (ref "U$3") (pin "8") (pinfunction "VDD2_8") (pintype "power_in"))
      (node (ref "U$5") (pin "16") (pinfunction "VDD2_16") (pintype "bidirectional"))
      (node (ref "U$6") (pin "8") (pinfunction "VDD2_8") (pintype "power_in"))
      (node (ref "U$7") (pin "8") (pinfunction "VDD2_8") (pintype "power_in"))
      (node (ref "VREGULATOR") (pin "2") (pinfunction "VO_2") (pintype "passive"))
    )
    (net (code "78") (name "/REV") (class "Default")
      (node (ref "RC") (pin "3") (pinfunction "3_3") (pintype "passive"))
      (node (ref "U$1") (pin "33") (pinfunction "33_33") (pintype "bidirectional"))
    )
    (net (code "79") (name "/RS-CS") (class "Default")
      (node (ref "RS") (pin "2") (pinfunction "2_2") (pintype "passive"))
      (node (ref "U$1") (pin "52") (pinfunction "52_52") (pintype "bidirectional"))
    )
    (net (code "80") (name "/RX0") (class "Default")
      (node (ref "SPINS") (pin "1") (pinfunction "1_1") (pintype "passive"))
      (node (ref "U$1") (pin "RX0") (pinfunction "RX0_RX0") (pintype "bidirectional"))
    )
    (net (code "81") (name "/RX2") (class "Default")
      (node (ref "SPINS") (pin "3") (pinfunction "3_3") (pintype "passive"))
      (node (ref "U$1") (pin "RX2") (pinfunction "RX2_RX2") (pintype "bidirectional"))
    )
    (net (code "82") (name "/RX3") (class "Default")
      (node (ref "GPS") (pin "2") (pinfunction "2_2") (pintype "passive"))
      (node (ref "U$1") (pin "RX3") (pinfunction "RX3_RX3") (pintype "bidirectional"))
    )
    (net (code "83") (name "/SAIL-IN") (class "Default")
      (node (ref "PWR-JUMPER") (pin "3") (pinfunction "3_3") (pintype "passive"))
      (node (ref "SAIL-PWR") (pin "2") (pinfunction "KL_2") (pintype "passive"))
    )
    (net (code "84") (name "/SCK") (class "Default")
      (node (ref "IMU") (pin "5") (pinfunction "5_5") (pintype "passive"))
      (node (ref "RS") (pin "5") (pinfunction "5_5") (pintype "passive"))
      (node (ref "U$1") (pin "SCK_ICSP") (pinfunction "SCK_ICSP_SCK_ICSP") (pintype "bidirectional"))
    )
    (net (code "85") (name "/SR1") (class "Default")
      (node (ref "HB1") (pin "5") (pinfunction "SR_5") (pintype "open_collector"))
      (node (ref "R17") (pin "1") (pinfunction "1_1") (pintype "passive"))
    )
    (net (code "86") (name "/SR2") (class "Default")
      (node (ref "HB2") (pin "5") (pinfunction "SR_5") (pintype "open_collector"))
      (node (ref "R16") (pin "1") (pinfunction "1_1") (pintype "passive"))
    )
    (net (code "87") (name "/TX0") (class "Default")
      (node (ref "SPINS") (pin "2") (pinfunction "2_2") (pintype "passive"))
      (node (ref "U$1") (pin "TX0") (pinfunction "TX0_TX0") (pintype "bidirectional"))
    )
    (net (code "88") (name "/TX2") (class "Default")
      (node (ref "SPINS") (pin "4") (pinfunction "4_4") (pintype "passive"))
      (node (ref "U$1") (pin "TX2") (pinfunction "TX2_TX2") (pintype "bidirectional"))
    )
    (net (code "89") (name "/TX3") (class "Default")
      (node (ref "GPS") (pin "3") (pinfunction "3_3") (pintype "passive"))
      (node (ref "U$1") (pin "TX3") (pinfunction "TX3_TX3") (pintype "bidirectional"))
    )
    (net (code "90") (name "/VIN") (class "Default")
      (node (ref "U$1") (pin "VIN") (pinfunction "VIN_VIN") (pintype "bidirectional"))
      (node (ref "VIN-JUMPER") (pin "2") (pinfunction "2_2") (pintype "passive"))
    )
    (net (code "91") (name "Net-(C34-Pad1)") (class "Default")
      (node (ref "C34") (pin "1") (pinfunction "1_1") (pintype "passive"))
      (node (ref "R24") (pin "2") (pinfunction "2_2") (pintype "passive"))
      (node (ref "U$1") (pin "A10") (pinfunction "A10_A10") (pintype "bidirectional"))
    )
    (net (code "92") (name "Net-(HB1-OUT)") (class "Default")
      (node (ref "HB1") (pin "4") (pinfunction "OUT_4") (pintype "output"))
      (node (ref "SAILMOTOR") (pin "1") (pinfunction "KL_1") (pintype "passive"))
    )
    (net (code "93") (name "Net-(LED1-PadA)") (class "Default")
      (node (ref "LED1") (pin "A") (pinfunction "A_A") (pintype "passive"))
      (node (ref "R1") (pin "2") (pinfunction "2_2") (pintype "passive"))
    )
    (net (code "94") (name "Net-(LED2-PadA)") (class "Default")
      (node (ref "LED2") (pin "A") (pinfunction "A_A") (pintype "passive"))
      (node (ref "R2") (pin "2") (pinfunction "2_2") (pintype "passive"))
    )
    (net (code "95") (name "Net-(LED3-PadA)") (class "Default")
      (node (ref "LED3") (pin "A") (pinfunction "A_A") (pintype "passive"))
      (node (ref "R3") (pin "2") (pinfunction "2_2") (pintype "passive"))
    )
    (net (code "96") (name "Net-(LED4-PadA)") (class "Default")
      (node (ref "LED4") (pin "A") (pinfunction "A_A") (pintype "passive"))
      (node (ref "R19") (pin "2") (pinfunction "2_2") (pintype "passive"))
    )
    (net (code "97") (name "Net-(LED5-PadA)") (class "Default")
      (node (ref "LED5") (pin "A") (pinfunction "A_A") (pintype "passive"))
      (node (ref "R20") (pin "2") (pinfunction "2_2") (pintype "passive"))
    )
    (net (code "98") (name "Net-(R2-Pad1)") (class "Default")
      (node (ref "R2") (pin "1") (pinfunction "1_1") (pintype "passive"))
      (node (ref "U$1") (pin "35") (pinfunction "35_35") (pintype "bidirectional"))
    )
    (net (code "99") (name "Net-(R3-Pad1)") (class "Default")
      (node (ref "R3") (pin "1") (pinfunction "1_1") (pintype "passive"))
      (node (ref "U$1") (pin "36") (pinfunction "36_36") (pintype "bidirectional"))
    )
    (net (code "100") (name "Net-(U$5-+IN)") (class "Default")
      (node (ref "R21") (pin "2") (pinfunction "2_2") (pintype "passive"))
      (node (ref "R22") (pin "1") (pinfunction "1_1") (pintype "passive"))
      (node (ref "U$5") (pin "12") (pinfunction "+IN_12") (pintype "bidirectional"))
    )
    (net (code "101") (name "Net-(U$5--IN)") (class "Default")
      (node (ref "U$5") (pin "10") (pinfunction "COMP_10") (pintype "bidirectional"))
      (node (ref "U$5") (pin "11") (pinfunction "-IN_11") (pintype "bidirectional"))
    )
    (net (code "102") (name "Net-(U$5-VREG1)") (class "Default")
      (node (ref "C30") (pin "1") (pinfunction "1_1") (pintype "passive"))
      (node (ref "U$5") (pin "3") (pinfunction "VREG1_3") (pintype "bidirectional"))
    )
    (net (code "103") (name "Net-(U$5-VREG2)") (class "Default")
      (node (ref "C32") (pin "1") (pinfunction "1_1") (pintype "passive"))
      (node (ref "U$5") (pin "14") (pinfunction "VREG2_14") (pintype "bidirectional"))
    )
    (net (code "104") (name "unconnected-(DC-CONV-Pad1)") (class "Default")
      (node (ref "DC-CONV") (pin "1") (pinfunction "1_1") (pintype "passive"))
    )
    (net (code "105") (name "unconnected-(DC-CONV-Pad3)") (class "Default")
      (node (ref "DC-CONV") (pin "3") (pinfunction "3_3") (pintype "passive"))
    )
    (net (code "106") (name "unconnected-(DC-CONV-Pad4)") (class "Default")
      (node (ref "DC-CONV") (pin "4") (pinfunction "4_4") (pintype "passive"))
    )
    (net (code "107") (name "unconnected-(DC-CONV-Pad5)") (class "Default")
      (node (ref "DC-CONV") (pin "5") (pinfunction "5_5") (pintype "passive"))
    )
    (net (code "108") (name "unconnected-(DC-CONV-Pad6)") (class "Default")
      (node (ref "DC-CONV") (pin "6") (pinfunction "6_6") (pintype "passive"))
    )
    (net (code "109") (name "unconnected-(DC-CONV-Pad7)") (class "Default")
      (node (ref "DC-CONV") (pin "7") (pinfunction "7_7") (pintype "passive"))
    )
    (net (code "110") (name "unconnected-(DC-CONV-Pad8)") (class "Default")
      (node (ref "DC-CONV") (pin "8") (pinfunction "8_8") (pintype "passive"))
    )
    (net (code "111") (name "unconnected-(DC-CONV-Pad9)") (class "Default")
      (node (ref "DC-CONV") (pin "9") (pinfunction "9_9") (pintype "passive"))
    )
    (net (code "112") (name "unconnected-(DC-CONV-Pad10)") (class "Default")
      (node (ref "DC-CONV") (pin "10") (pinfunction "10_10") (pintype "passive"))
    )
    (net (code "113") (name "unconnected-(DC-CONV-Pad11)") (class "Default")
      (node (ref "DC-CONV") (pin "11") (pinfunction "11_11") (pintype "passive"))
    )
    (net (code "114") (name "unconnected-(DC-CONV-Pad12)") (class "Default")
      (node (ref "DC-CONV") (pin "12") (pinfunction "12_12") (pintype "passive"))
    )
    (net (code "115") (name "unconnected-(DC-CONV-Pad13)") (class "Default")
      (node (ref "DC-CONV") (pin "13") (pinfunction "13_13") (pintype "passive"))
    )
    (net (code "116") (name "unconnected-(DC-CONV-Pad15)") (class "Default")
      (node (ref "DC-CONV") (pin "15") (pinfunction "15_15") (pintype "passive"))
    )
    (net (code "117") (name "unconnected-(DC-CONV-Pad17)") (class "Default")
      (node (ref "DC-CONV") (pin "17") (pinfunction "17_17") (pintype "passive"))
    )
    (net (code "118") (name "unconnected-(DC-CONV-Pad18)") (class "Default")
      (node (ref "DC-CONV") (pin "18") (pinfunction "18_18") (pintype "passive"))
    )
    (net (code "119") (name "unconnected-(DC-CONV-Pad19)") (class "Default")
      (node (ref "DC-CONV") (pin "19") (pinfunction "19_19") (pintype "passive"))
    )
    (net (code "120") (name "unconnected-(DC-CONV-Pad20)") (class "Default")
      (node (ref "DC-CONV") (pin "20") (pinfunction "20_20") (pintype "passive"))
    )
    (net (code "121") (name "unconnected-(DC-CONV-Pad21)") (class "Default")
      (node (ref "DC-CONV") (pin "21") (pinfunction "21_21") (pintype "passive"))
    )
    (net (code "122") (name "unconnected-(DC-CONV-Pad22)") (class "Default")
      (node (ref "DC-CONV") (pin "22") (pinfunction "22_22") (pintype "passive"))
    )
    (net (code "123") (name "unconnected-(DC-CONV-Pad24)") (class "Default")
      (node (ref "DC-CONV") (pin "24") (pinfunction "24_24") (pintype "passive"))
    )
    (net (code "124") (name "unconnected-(HB1-IS-Pad6)") (class "Default")
      (node (ref "HB1") (pin "6") (pinfunction "IS_6") (pintype "output"))
    )
    (net (code "125") (name "unconnected-(HB2-IS-Pad6)") (class "Default")
      (node (ref "HB2") (pin "6") (pinfunction "IS_6") (pintype "output"))
    )
    (net (code "126") (name "unconnected-(LR1-DOUT-Pad13)") (class "Default")
      (node (ref "LR1") (pin "13") (pinfunction "DOUT_13") (pintype "output"))
    )
    (net (code "127") (name "unconnected-(LR1-~{EN}-Pad12)") (class "Default")
      (node (ref "LR1") (pin "12") (pinfunction "~{EN}_12") (pintype "input"))
    )
    (net (code "128") (name "unconnected-(LR2-DOUT-Pad13)") (class "Default")
      (node (ref "LR2") (pin "13") (pinfunction "DOUT_13") (pintype "output"))
    )
    (net (code "129") (name "unconnected-(LR2-~{EN}-Pad12)") (class "Default")
      (node (ref "LR2") (pin "12") (pinfunction "~{EN}_12") (pintype "input"))
    )
    (net (code "130") (name "unconnected-(U$1-Pad3)") (class "Default")
      (node (ref "U$1") (pin "3") (pinfunction "3_3") (pintype "bidirectional"))
    )
    (net (code "131") (name "unconnected-(U$1-Pad5V_A)") (class "Default")
      (node (ref "U$1") (pin "5V_A") (pinfunction "5V_A_5V_A") (pintype "bidirectional"))
    )
    (net (code "132") (name "unconnected-(U$1-Pad5V_B)") (class "Default")
      (node (ref "U$1") (pin "5V_B") (pinfunction "5V_B_5V_B") (pintype "bidirectional"))
    )
    (net (code "133") (name "unconnected-(U$1-Pad6)") (class "Default")
      (node (ref "U$1") (pin "6") (pinfunction "6_6") (pintype "bidirectional"))
    )
    (net (code "134") (name "unconnected-(U$1-Pad7)") (class "Default")
      (node (ref "U$1") (pin "7") (pinfunction "7_7") (pintype "bidirectional"))
    )
    (net (code "135") (name "unconnected-(U$1-Pad12)") (class "Default")
      (node (ref "U$1") (pin "12") (pinfunction "12_12") (pintype "bidirectional"))
    )
    (net (code "136") (name "unconnected-(U$1-Pad23)") (class "Default")
      (node (ref "U$1") (pin "23") (pinfunction "23_23") (pintype "bidirectional"))
    )
    (net (code "137") (name "unconnected-(U$1-Pad24)") (class "Default")
      (node (ref "U$1") (pin "24") (pinfunction "24_24") (pintype "bidirectional"))
    )
    (net (code "138") (name "unconnected-(U$1-Pad41)") (class "Default")
      (node (ref "U$1") (pin "41") (pinfunction "41_41") (pintype "bidirectional"))
    )
    (net (code "139") (name "unconnected-(U$1-Pad42)") (class "Default")
      (node (ref "U$1") (pin "42") (pinfunction "42_42") (pintype "bidirectional"))
    )
    (net (code "140") (name "unconnected-(U$1-Pad43)") (class "Default")
      (node (ref "U$1") (pin "43") (pinfunction "43_43") (pintype "bidirectional"))
    )
    (net (code "141") (name "unconnected-(U$1-Pad45)") (class "Default")
      (node (ref "U$1") (pin "45") (pinfunction "45_45") (pintype "bidirectional"))
    )
    (net (code "142") (name "unconnected-(U$1-PadA5)") (class "Default")
      (node (ref "U$1") (pin "A5") (pinfunction "A5_A5") (pintype "bidirectional"))
    )
    (net (code "143") (name "unconnected-(U$1-PadAREF)") (class "Default")
      (node (ref "U$1") (pin "AREF") (pinfunction "AREF_AREF") (pintype "bidirectional"))
    )
    (net (code "144") (name "unconnected-(U$1-PadCANRX)") (class "Default")
      (node (ref "U$1") (pin "CANRX") (pinfunction "CANRX_CANRX") (pintype "bidirectional"))
    )
    (net (code "145") (name "unconnected-(U$1-PadCANTX)") (class "Default")
      (node (ref "U$1") (pin "CANTX") (pinfunction "CANTX_CANTX") (pintype "bidirectional"))
    )
    (net (code "146") (name "unconnected-(U$1-PadDAC0)") (class "Default")
      (node (ref "U$1") (pin "DAC0") (pinfunction "DAC0_DAC0") (pintype "bidirectional"))
    )
    (net (code "147") (name "unconnected-(U$1-PadGND1)") (class "Default")
      (node (ref "U$1") (pin "GND1") (pinfunction "GND1_GND1") (pintype "bidirectional"))
    )
    (net (code "148") (name "unconnected-(U$1-PadGND_A)") (class "Default")
      (node (ref "U$1") (pin "GND_A") (pinfunction "GND_A_GND_A") (pintype "bidirectional"))
    )
    (net (code "149") (name "unconnected-(U$1-PadGND_B)") (class "Default")
      (node (ref "U$1") (pin "GND_B") (pinfunction "GND_B_GND_B") (pintype "bidirectional"))
    )
    (net (code "150") (name "unconnected-(U$1-PadGND_DEBUG)") (class "Default")
      (node (ref "U$1") (pin "GND_DEBUG") (pinfunction "GND_DEBUG_GND_DEBUG") (pintype "bidirectional"))
    )
    (net (code "151") (name "unconnected-(U$1-PadGND_ICSP)") (class "Default")
      (node (ref "U$1") (pin "GND_ICSP") (pinfunction "GND_ICSP_GND_ICSP") (pintype "bidirectional"))
    )
    (net (code "152") (name "unconnected-(U$1-PadIOREF)") (class "Default")
      (node (ref "U$1") (pin "IOREF") (pinfunction "IOREF_IOREF") (pintype "bidirectional"))
    )
    (net (code "153") (name "unconnected-(U$1-PadNC)") (class "Default")
      (node (ref "U$1") (pin "NC") (pinfunction "NC_NC") (pintype "bidirectional"))
    )
    (net (code "154") (name "unconnected-(U$1-PadRESET)") (class "Default")
      (node (ref "U$1") (pin "RESET") (pinfunction "RESET_RESET") (pintype "bidirectional"))
    )
    (net (code "155") (name "unconnected-(U$1-PadRESET_DEBUG)") (class "Default")
      (node (ref "U$1") (pin "RESET_DEBUG") (pinfunction "RESET_DEBUG_RESET_DEBUG") (pintype "bidirectional"))
    )
    (net (code "156") (name "unconnected-(U$1-PadRESET_ICSP)") (class "Default")
      (node (ref "U$1") (pin "RESET_ICSP") (pinfunction "RESET_ICSP_RESET_ICSP") (pintype "bidirectional"))
    )
    (net (code "157") (name "unconnected-(U$1-PadRX1)") (class "Default")
      (node (ref "U$1") (pin "RX1") (pinfunction "RX1_RX1") (pintype "bidirectional"))
    )
    (net (code "158") (name "unconnected-(U$1-PadSCL)") (class "Default")
      (node (ref "U$1") (pin "SCL") (pinfunction "SCL_SCL") (pintype "bidirectional"))
    )
    (net (code "159") (name "unconnected-(U$1-PadSCL1)") (class "Default")
      (node (ref "U$1") (pin "SCL1") (pinfunction "SCL1_SCL1") (pintype "bidirectional"))
    )
    (net (code "160") (name "unconnected-(U$1-PadSDA)") (class "Default")
      (node (ref "U$1") (pin "SDA") (pinfunction "SDA_SDA") (pintype "bidirectional"))
    )
    (net (code "161") (name "unconnected-(U$1-PadSDA1)") (class "Default")
      (node (ref "U$1") (pin "SDA1") (pinfunction "SDA1_SDA1") (pintype "bidirectional"))
    )
    (net (code "162") (name "unconnected-(U$1-PadSWCLK_DEBUG)") (class "Default")
      (node (ref "U$1") (pin "SWCLK_DEBUG") (pinfunction "SWCLK_DEBUG_SWCLK_DEBUG") (pintype "bidirectional"))
    )
    (net (code "163") (name "unconnected-(U$1-PadSWDIO_DEBUG)") (class "Default")
      (node (ref "U$1") (pin "SWDIO_DEBUG") (pinfunction "SWDIO_DEBUG_SWDIO_DEBUG") (pintype "bidirectional"))
    )
    (net (code "164") (name "unconnected-(U$1-PadTX1)") (class "Default")
      (node (ref "U$1") (pin "TX1") (pinfunction "TX1_TX1") (pintype "bidirectional"))
    )
    (net (code "165") (name "unconnected-(U$5-EAOUT2-Pad6)") (class "Default")
      (node (ref "U$5") (pin "6") (pinfunction "EAOUT2_6") (pintype "bidirectional"))
    )
    (net (code "166") (name "unconnected-(U$5-NC2-Pad5)") (class "Default")
      (node (ref "U$5") (pin "5") (pinfunction "NC2_5") (pintype "bidirectional"))
    )
    (net (code "167") (name "unconnected-(U$5-REFOUT-Pad13)") (class "Default")
      (node (ref "U$5") (pin "13") (pinfunction "REFOUT_13") (pintype "bidirectional"))
    )
    (net (code "168") (name "unconnected-(U$5-REFOUT1-Pad4)") (class "Default")
      (node (ref "U$5") (pin "4") (pinfunction "REFOUT1_4") (pintype "bidirectional"))
    )
  )
)
